# tile-controller.net
KiCad netlist of a schematic drawn in EAGLE
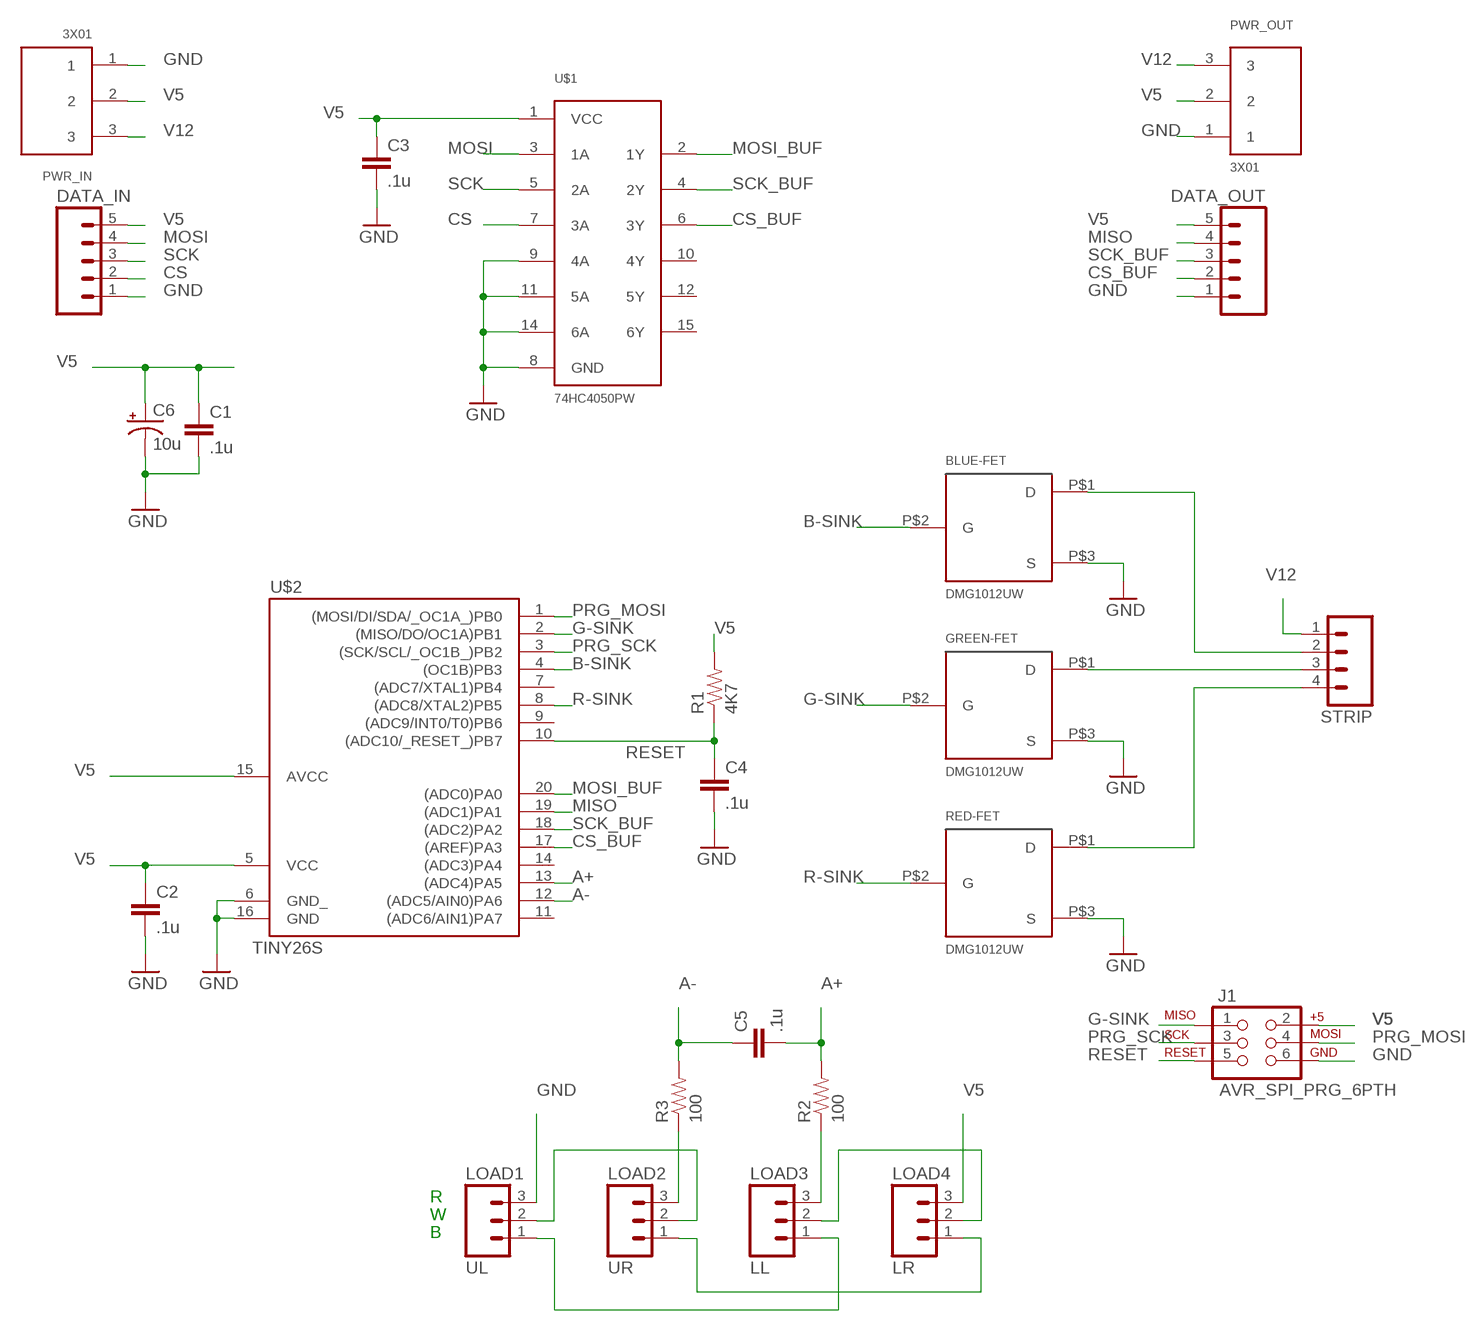
[diagram p0: schematic, sheet 1]

(export (version "E")
  (design (tool "Eeschema 10.0.6"))
  (components
    (comp (ref "BLUE-FET")
      (value "DMG1012UW")
      (footprint "eagle-import:SOT-323")
      (libsource (lib "eagle-import") (part "DMG1012UW"))
    )
    (comp (ref "C1")
      (value ".1u")
      (footprint "eagle-import:0805")
      (libsource (lib "eagle-import") (part "CAP0805"))
    )
    (comp (ref "C2")
      (value ".1u")
      (footprint "eagle-import:0805")
      (libsource (lib "eagle-import") (part "CAP0805"))
    )
    (comp (ref "C3")
      (value ".1u")
      (footprint "eagle-import:0805")
      (libsource (lib "eagle-import") (part "CAP0805"))
    )
    (comp (ref "C4")
      (value ".1u")
      (footprint "eagle-import:0805")
      (libsource (lib "eagle-import") (part "CAP0805"))
    )
    (comp (ref "C5")
      (value ".1u")
      (footprint "eagle-import:0805")
      (libsource (lib "eagle-import") (part "CAP0805"))
    )
    (comp (ref "C6")
      (value "10u")
      (footprint "eagle-import:EIA3216")
      (libsource (lib "eagle-import") (part "CAP_POL1206"))
    )
    (comp (ref "DATA_IN")
      (value "M05PTH")
      (footprint "eagle-import:1X05")
      (libsource (lib "eagle-import") (part "M05PTH"))
    )
    (comp (ref "DATA_OUT")
      (value "M05PTH")
      (footprint "eagle-import:1X05")
      (libsource (lib "eagle-import") (part "M05PTH"))
    )
    (comp (ref "GREEN-FET")
      (value "DMG1012UW")
      (footprint "eagle-import:SOT-323")
      (libsource (lib "eagle-import") (part "DMG1012UW"))
    )
    (comp (ref "J1")
      (value "AVR_SPI_PRG_6PTH")
      (footprint "eagle-import:2X3")
      (libsource (lib "eagle-import") (part "AVR_SPI_PRG_6PTH"))
    )
    (comp (ref "LOAD1")
      (value "UL")
      (footprint "eagle-import:1X03")
      (libsource (lib "eagle-import") (part "M03PTH"))
    )
    (comp (ref "LOAD2")
      (value "UR")
      (footprint "eagle-import:1X03")
      (libsource (lib "eagle-import") (part "M03PTH"))
    )
    (comp (ref "LOAD3")
      (value "LL")
      (footprint "eagle-import:1X03")
      (libsource (lib "eagle-import") (part "M03PTH"))
    )
    (comp (ref "LOAD4")
      (value "LR")
      (footprint "eagle-import:1X03")
      (libsource (lib "eagle-import") (part "M03PTH"))
    )
    (comp (ref "PWR_IN")
      (value "3X01")
      (footprint "eagle-import:3X01-18AWG")
      (libsource (lib "eagle-import") (part "3X01"))
    )
    (comp (ref "PWR_OUT")
      (value "3X01")
      (footprint "eagle-import:3X01-18AWG")
      (libsource (lib "eagle-import") (part "3X01"))
    )
    (comp (ref "R1")
      (value "4K7")
      (footprint "eagle-import:0805")
      (libsource (lib "eagle-import") (part "RESISTOR"))
    )
    (comp (ref "R2")
      (value "100")
      (footprint "eagle-import:0805")
      (libsource (lib "eagle-import") (part "RESISTOR"))
    )
    (comp (ref "R3")
      (value "100")
      (footprint "eagle-import:0805")
      (libsource (lib "eagle-import") (part "RESISTOR"))
    )
    (comp (ref "RED-FET")
      (value "DMG1012UW")
      (footprint "eagle-import:SOT-323")
      (libsource (lib "eagle-import") (part "DMG1012UW"))
    )
    (comp (ref "STRIP")
      (value "M04PTH")
      (footprint "eagle-import:1X04")
      (libsource (lib "eagle-import") (part "M04PTH"))
    )
    (comp (ref "U$1")
      (value "74HC4050PW")
      (footprint "eagle-import:TSSOP16.2")
      (libsource (lib "eagle-import") (part "74HC4050PW"))
    )
    (comp (ref "U$2")
      (value "TINY26S")
      (footprint "eagle-import:SO20L$")
      (libsource (lib "eagle-import") (part "TINY26S"))
    )
  )
  (nets
    (net (code "1") (name "/A+") (class "Default")
      (node (ref "C5") (pin "2") (pinfunction "2_2") (pintype "passive"))
      (node (ref "R2") (pin "2") (pinfunction "2_2") (pintype "passive"))
      (node (ref "U$2") (pin "13") (pinfunction "(ADC4)PA5_13") (pintype "bidirectional"))
    )
    (net (code "2") (name "/A-") (class "Default")
      (node (ref "C5") (pin "1") (pinfunction "1_1") (pintype "passive"))
      (node (ref "R3") (pin "2") (pinfunction "2_2") (pintype "passive"))
      (node (ref "U$2") (pin "12") (pinfunction "(ADC5/AIN0)PA6_12") (pintype "bidirectional"))
    )
    (net (code "3") (name "/B-SINK") (class "Default")
      (node (ref "BLUE-FET") (pin "P$2") (pinfunction "G_P$2") (pintype "bidirectional"))
      (node (ref "U$2") (pin "4") (pinfunction "(OC1B)PB3_4") (pintype "bidirectional"))
    )
    (net (code "4") (name "/CS") (class "Default")
      (node (ref "DATA_IN") (pin "2") (pinfunction "2_2") (pintype "passive"))
      (node (ref "U$1") (pin "7") (pinfunction "3A_7") (pintype "input"))
    )
    (net (code "5") (name "/CS_BUF") (class "Default")
      (node (ref "DATA_OUT") (pin "2") (pinfunction "2_2") (pintype "passive"))
      (node (ref "U$1") (pin "6") (pinfunction "3Y_6") (pintype "output"))
      (node (ref "U$2") (pin "17") (pinfunction "(AREF)PA3_17") (pintype "bidirectional"))
    )
    (net (code "6") (name "/G-SINK") (class "Default")
      (node (ref "GREEN-FET") (pin "P$2") (pinfunction "G_P$2") (pintype "bidirectional"))
      (node (ref "J1") (pin "1") (pinfunction "1_1") (pintype "passive"))
      (node (ref "U$2") (pin "2") (pinfunction "(MISO/DO/OC1A)PB1_2") (pintype "bidirectional"))
    )
    (net (code "7") (name "/MISO") (class "Default")
      (node (ref "DATA_OUT") (pin "4") (pinfunction "4_4") (pintype "passive"))
      (node (ref "U$2") (pin "19") (pinfunction "(ADC1)PA1_19") (pintype "bidirectional"))
    )
    (net (code "8") (name "/MOSI") (class "Default")
      (node (ref "DATA_IN") (pin "4") (pinfunction "4_4") (pintype "passive"))
      (node (ref "U$1") (pin "3") (pinfunction "1A_3") (pintype "input"))
    )
    (net (code "9") (name "/MOSI_BUF") (class "Default")
      (node (ref "U$1") (pin "2") (pinfunction "1Y_2") (pintype "output"))
      (node (ref "U$2") (pin "20") (pinfunction "(ADC0)PA0_20") (pintype "bidirectional"))
    )
    (net (code "10") (name "/PRG_MOSI") (class "Default")
      (node (ref "J1") (pin "4") (pinfunction "4_4") (pintype "passive"))
      (node (ref "U$2") (pin "1") (pinfunction "(MOSI/DI/SDA/_OC1A_)PB0_1") (pintype "bidirectional"))
    )
    (net (code "11") (name "/PRG_SCK") (class "Default")
      (node (ref "J1") (pin "3") (pinfunction "3_3") (pintype "passive"))
      (node (ref "U$2") (pin "3") (pinfunction "(SCK/SCL/_OC1B_)PB2_3") (pintype "bidirectional"))
    )
    (net (code "12") (name "/R-SINK") (class "Default")
      (node (ref "RED-FET") (pin "P$2") (pinfunction "G_P$2") (pintype "bidirectional"))
      (node (ref "U$2") (pin "8") (pinfunction "(ADC8/XTAL2)PB5_8") (pintype "bidirectional"))
    )
    (net (code "13") (name "/RESET") (class "Default")
      (node (ref "C4") (pin "1") (pinfunction "1_1") (pintype "passive"))
      (node (ref "J1") (pin "5") (pinfunction "5_5") (pintype "passive"))
      (node (ref "R1") (pin "1") (pinfunction "1_1") (pintype "passive"))
      (node (ref "U$2") (pin "10") (pinfunction "(ADC10/_RESET_)PB7_10") (pintype "bidirectional"))
    )
    (net (code "14") (name "/SCK") (class "Default")
      (node (ref "DATA_IN") (pin "3") (pinfunction "3_3") (pintype "passive"))
      (node (ref "U$1") (pin "5") (pinfunction "2A_5") (pintype "input"))
    )
    (net (code "15") (name "/SCK_BUF") (class "Default")
      (node (ref "DATA_OUT") (pin "3") (pinfunction "3_3") (pintype "passive"))
      (node (ref "U$1") (pin "4") (pinfunction "2Y_4") (pintype "output"))
      (node (ref "U$2") (pin "18") (pinfunction "(ADC2)PA2_18") (pintype "bidirectional"))
    )
    (net (code "16") (name "/V5") (class "Default")
      (node (ref "C1") (pin "1") (pinfunction "1_1") (pintype "passive"))
      (node (ref "C2") (pin "1") (pinfunction "1_1") (pintype "passive"))
      (node (ref "C3") (pin "1") (pinfunction "1_1") (pintype "passive"))
      (node (ref "C6") (pin "A") (pinfunction "+_A") (pintype "passive"))
      (node (ref "DATA_IN") (pin "5") (pinfunction "5_5") (pintype "passive"))
      (node (ref "DATA_OUT") (pin "5") (pinfunction "5_5") (pintype "passive"))
      (node (ref "J1") (pin "2") (pinfunction "2_2") (pintype "passive"))
      (node (ref "LOAD4") (pin "3") (pinfunction "3_3") (pintype "passive"))
      (node (ref "PWR_IN") (pin "2") (pinfunction "2_2") (pintype "bidirectional"))
      (node (ref "PWR_OUT") (pin "2") (pinfunction "2_2") (pintype "bidirectional"))
      (node (ref "R1") (pin "2") (pinfunction "2_2") (pintype "passive"))
      (node (ref "U$1") (pin "1") (pinfunction "VCC_1") (pintype "power_in"))
      (node (ref "U$2") (pin "15") (pinfunction "AVCC_15") (pintype "power_in"))
      (node (ref "U$2") (pin "5") (pinfunction "VCC_5") (pintype "power_in"))
    )
    (net (code "17") (name "/V12") (class "Default")
      (node (ref "PWR_IN") (pin "3") (pinfunction "3_3") (pintype "bidirectional"))
      (node (ref "PWR_OUT") (pin "3") (pinfunction "3_3") (pintype "bidirectional"))
      (node (ref "STRIP") (pin "1") (pinfunction "1_1") (pintype "passive"))
    )
    (net (code "18") (name "GND") (class "Default")
      (node (ref "BLUE-FET") (pin "P$3") (pinfunction "S_P$3") (pintype "bidirectional"))
      (node (ref "C1") (pin "2") (pinfunction "2_2") (pintype "passive"))
      (node (ref "C2") (pin "2") (pinfunction "2_2") (pintype "passive"))
      (node (ref "C3") (pin "2") (pinfunction "2_2") (pintype "passive"))
      (node (ref "C4") (pin "2") (pinfunction "2_2") (pintype "passive"))
      (node (ref "C6") (pin "C") (pinfunction "-_C") (pintype "passive"))
      (node (ref "DATA_IN") (pin "1") (pinfunction "1_1") (pintype "passive"))
      (node (ref "DATA_OUT") (pin "1") (pinfunction "1_1") (pintype "passive"))
      (node (ref "GREEN-FET") (pin "P$3") (pinfunction "S_P$3") (pintype "bidirectional"))
      (node (ref "J1") (pin "6") (pinfunction "6_6") (pintype "passive"))
      (node (ref "LOAD1") (pin "3") (pinfunction "3_3") (pintype "passive"))
      (node (ref "PWR_IN") (pin "1") (pinfunction "1_1") (pintype "bidirectional"))
      (node (ref "PWR_OUT") (pin "1") (pinfunction "1_1") (pintype "bidirectional"))
      (node (ref "RED-FET") (pin "P$3") (pinfunction "S_P$3") (pintype "bidirectional"))
      (node (ref "U$1") (pin "11") (pinfunction "5A_11") (pintype "input"))
      (node (ref "U$1") (pin "14") (pinfunction "6A_14") (pintype "input"))
      (node (ref "U$1") (pin "8") (pinfunction "GND_8") (pintype "power_in"))
      (node (ref "U$1") (pin "9") (pinfunction "4A_9") (pintype "input"))
      (node (ref "U$2") (pin "16") (pinfunction "GND_16") (pintype "power_in"))
      (node (ref "U$2") (pin "6") (pinfunction "GND__6") (pintype "power_in"))
    )
    (net (code "19") (name "Net-(BLUE-FET-D)") (class "Default")
      (node (ref "BLUE-FET") (pin "P$1") (pinfunction "D_P$1") (pintype "bidirectional"))
      (node (ref "STRIP") (pin "2") (pinfunction "2_2") (pintype "passive"))
    )
    (net (code "20") (name "Net-(GREEN-FET-D)") (class "Default")
      (node (ref "GREEN-FET") (pin "P$1") (pinfunction "D_P$1") (pintype "bidirectional"))
      (node (ref "STRIP") (pin "3") (pinfunction "3_3") (pintype "passive"))
    )
    (net (code "21") (name "Net-(LOAD1-Pad1)") (class "Default")
      (node (ref "LOAD1") (pin "1") (pinfunction "1_1") (pintype "passive"))
      (node (ref "LOAD3") (pin "1") (pinfunction "1_1") (pintype "passive"))
    )
    (net (code "22") (name "Net-(LOAD1-Pad2)") (class "Default")
      (node (ref "LOAD1") (pin "2") (pinfunction "2_2") (pintype "passive"))
      (node (ref "LOAD2") (pin "2") (pinfunction "2_2") (pintype "passive"))
    )
    (net (code "23") (name "Net-(LOAD2-Pad1)") (class "Default")
      (node (ref "LOAD2") (pin "1") (pinfunction "1_1") (pintype "passive"))
      (node (ref "LOAD4") (pin "1") (pinfunction "1_1") (pintype "passive"))
    )
    (net (code "24") (name "Net-(LOAD2-Pad3)") (class "Default")
      (node (ref "LOAD2") (pin "3") (pinfunction "3_3") (pintype "passive"))
      (node (ref "R3") (pin "1") (pinfunction "1_1") (pintype "passive"))
    )
    (net (code "25") (name "Net-(LOAD3-Pad2)") (class "Default")
      (node (ref "LOAD3") (pin "2") (pinfunction "2_2") (pintype "passive"))
      (node (ref "LOAD4") (pin "2") (pinfunction "2_2") (pintype "passive"))
    )
    (net (code "26") (name "Net-(LOAD3-Pad3)") (class "Default")
      (node (ref "LOAD3") (pin "3") (pinfunction "3_3") (pintype "passive"))
      (node (ref "R2") (pin "1") (pinfunction "1_1") (pintype "passive"))
    )
    (net (code "27") (name "Net-(RED-FET-D)") (class "Default")
      (node (ref "RED-FET") (pin "P$1") (pinfunction "D_P$1") (pintype "bidirectional"))
      (node (ref "STRIP") (pin "4") (pinfunction "4_4") (pintype "passive"))
    )
    (net (code "28") (name "unconnected-(U$1-4Y-Pad10)") (class "Default")
      (node (ref "U$1") (pin "10") (pinfunction "4Y_10") (pintype "output"))
    )
    (net (code "29") (name "unconnected-(U$1-5Y-Pad12)") (class "Default")
      (node (ref "U$1") (pin "12") (pinfunction "5Y_12") (pintype "output"))
    )
    (net (code "30") (name "unconnected-(U$1-6Y-Pad15)") (class "Default")
      (node (ref "U$1") (pin "15") (pinfunction "6Y_15") (pintype "output"))
    )
    (net (code "31") (name "unconnected-(U$2-(ADC3)PA4-Pad14)") (class "Default")
      (node (ref "U$2") (pin "14") (pinfunction "(ADC3)PA4_14") (pintype "bidirectional"))
    )
    (net (code "32") (name "unconnected-(U$2-(ADC6{slash}AIN1)PA7-Pad11)") (class "Default")
      (node (ref "U$2") (pin "11") (pinfunction "(ADC6/AIN1)PA7_11") (pintype "bidirectional"))
    )
    (net (code "33") (name "unconnected-(U$2-(ADC7{slash}XTAL1)PB4-Pad7)") (class "Default")
      (node (ref "U$2") (pin "7") (pinfunction "(ADC7/XTAL1)PB4_7") (pintype "bidirectional"))
    )
    (net (code "34") (name "unconnected-(U$2-(ADC9{slash}INT0{slash}T0)PB6-Pad9)") (class "Default")
      (node (ref "U$2") (pin "9") (pinfunction "(ADC9/INT0/T0)PB6_9") (pintype "bidirectional"))
    )
  )
)
